# MicroD-25_Breakout_board.net
KiCad netlist of a schematic drawn in EAGLE
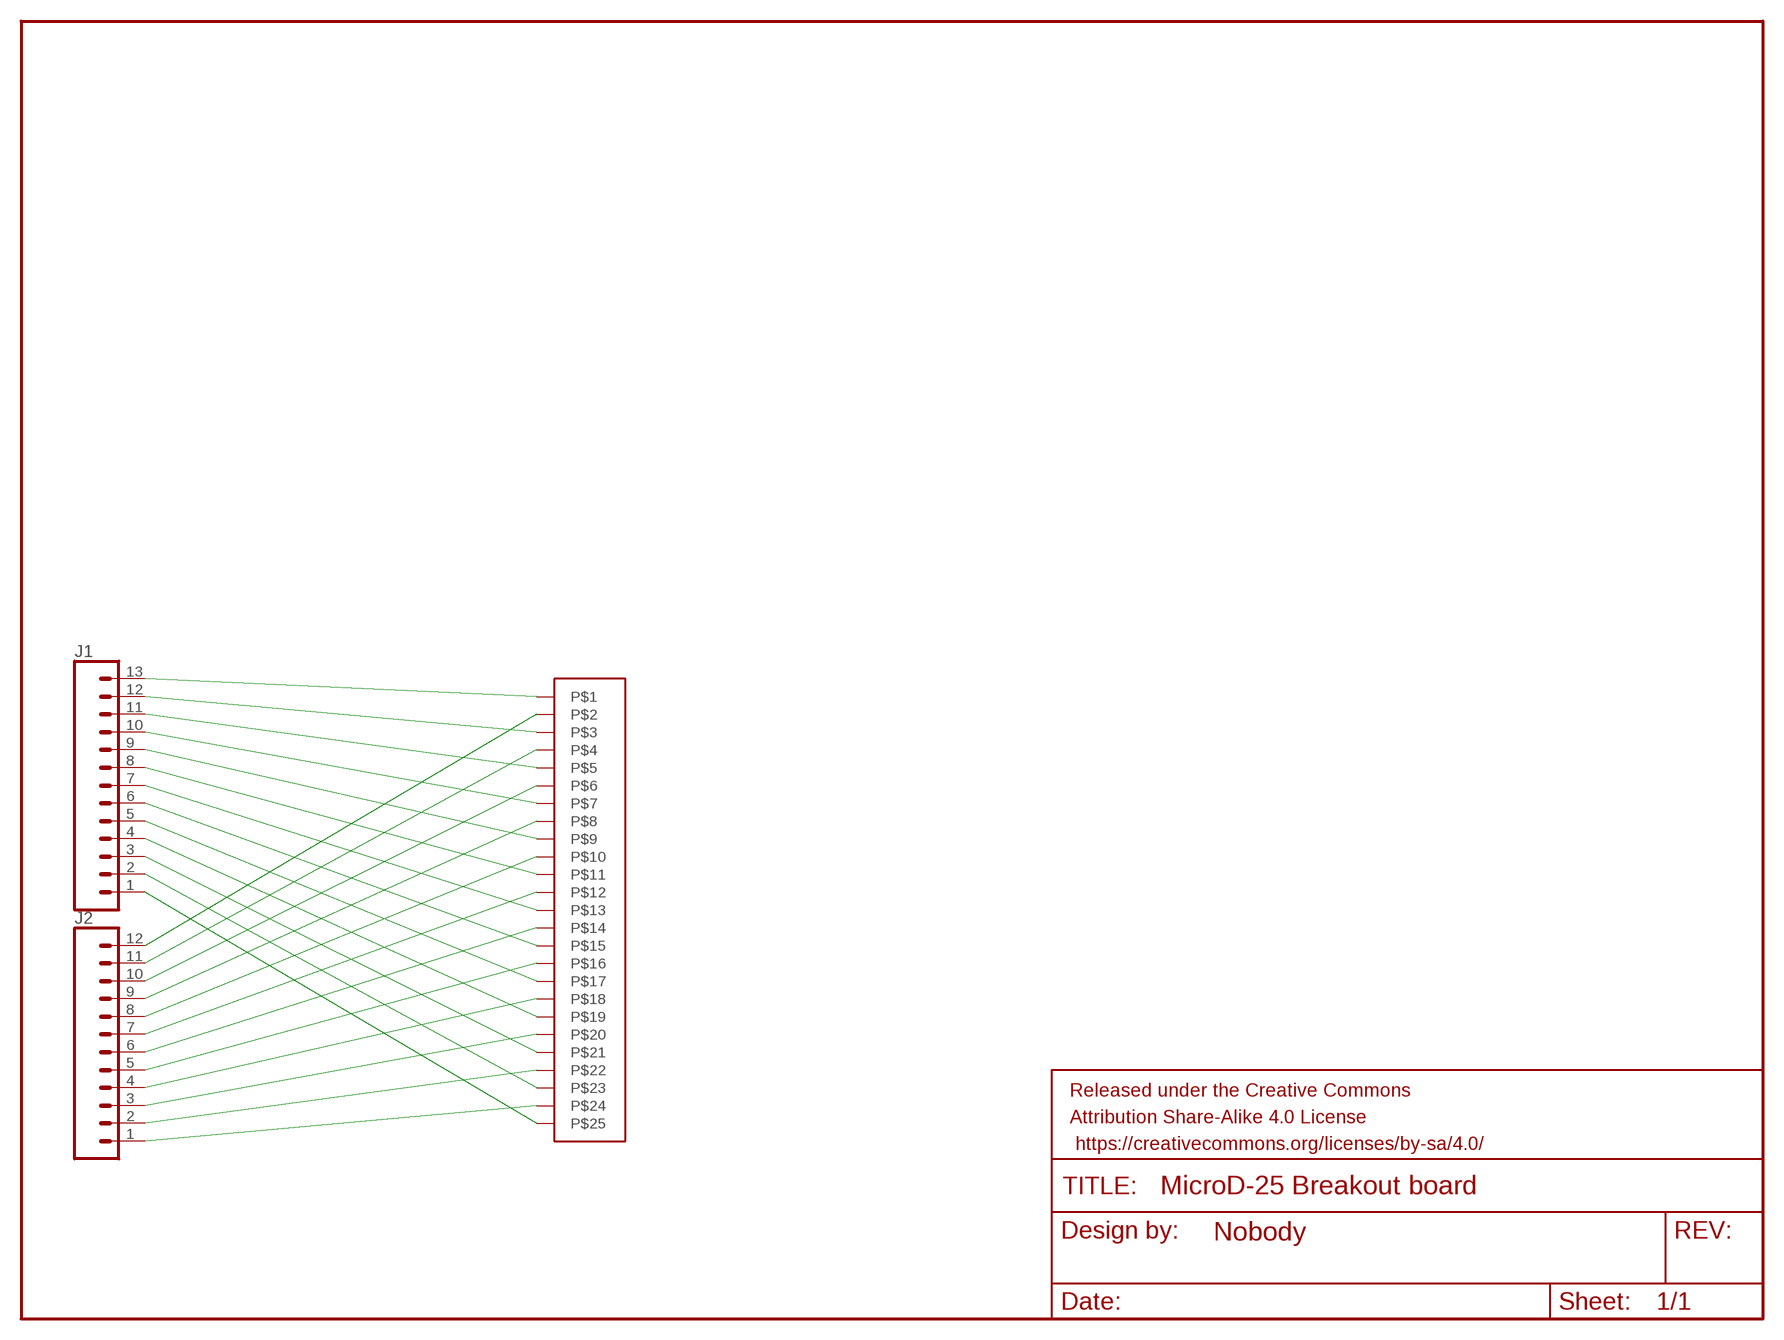
[diagram p0: schematic, sheet 1]

(export (version "E")
  (design (tool "Eeschema 10.0.6"))
  (components
    (comp (ref "FRAME1")
      (value "FRAME-LETTERNO_PACKAGE")
      (footprint "eagle-import:DUMMY")
      (fields (field (name "DESIGNER") "Nobody"))
      (libsource (lib "eagle-import") (part "FRAME-LETTERNO_PACKAGE"))
    )
    (comp (ref "J1")
      (value "CONN_13LONGPADS")
      (footprint "eagle-import:1X13-LONGPADS")
      (libsource (lib "eagle-import") (part "CONN_13LONGPADS"))
    )
    (comp (ref "J2")
      (value "CONN_12LONGPADS")
      (footprint "eagle-import:1X12_LONGPADS")
      (libsource (lib "eagle-import") (part "CONN_12LONGPADS"))
    )
    (comp (ref "U$1")
      (value "MICROD25_FM_RCPT")
      (footprint "eagle-import:MICROD25_FM_RCPT")
      (libsource (lib "eagle-import") (part "MICROD25_FM_RCPT"))
    )
  )
  (nets
    (net (code "1") (name "Net-(U$1-P$1)") (class "Default")
      (node (ref "J1") (pin "13") (pinfunction "13_13") (pintype "passive"))
      (node (ref "U$1") (pin "PIN1") (pinfunction "P$1_PIN1") (pintype "bidirectional"))
    )
    (net (code "2") (name "Net-(U$1-P$2)") (class "Default")
      (node (ref "J2") (pin "12") (pinfunction "12_12") (pintype "passive"))
      (node (ref "U$1") (pin "PIN2") (pinfunction "P$2_PIN2") (pintype "bidirectional"))
    )
    (net (code "3") (name "Net-(U$1-P$3)") (class "Default")
      (node (ref "J1") (pin "12") (pinfunction "12_12") (pintype "passive"))
      (node (ref "U$1") (pin "PIN3") (pinfunction "P$3_PIN3") (pintype "bidirectional"))
    )
    (net (code "4") (name "Net-(U$1-P$4)") (class "Default")
      (node (ref "J2") (pin "11") (pinfunction "11_11") (pintype "passive"))
      (node (ref "U$1") (pin "PIN4") (pinfunction "P$4_PIN4") (pintype "bidirectional"))
    )
    (net (code "5") (name "Net-(U$1-P$5)") (class "Default")
      (node (ref "J1") (pin "11") (pinfunction "11_11") (pintype "passive"))
      (node (ref "U$1") (pin "PIN5") (pinfunction "P$5_PIN5") (pintype "bidirectional"))
    )
    (net (code "6") (name "Net-(U$1-P$6)") (class "Default")
      (node (ref "J2") (pin "10") (pinfunction "10_10") (pintype "passive"))
      (node (ref "U$1") (pin "PIN6") (pinfunction "P$6_PIN6") (pintype "bidirectional"))
    )
    (net (code "7") (name "Net-(U$1-P$7)") (class "Default")
      (node (ref "J1") (pin "10") (pinfunction "10_10") (pintype "passive"))
      (node (ref "U$1") (pin "PIN7") (pinfunction "P$7_PIN7") (pintype "bidirectional"))
    )
    (net (code "8") (name "Net-(U$1-P$8)") (class "Default")
      (node (ref "J2") (pin "9") (pinfunction "9_9") (pintype "passive"))
      (node (ref "U$1") (pin "PIN8") (pinfunction "P$8_PIN8") (pintype "bidirectional"))
    )
    (net (code "9") (name "Net-(U$1-P$9)") (class "Default")
      (node (ref "J1") (pin "9") (pinfunction "9_9") (pintype "passive"))
      (node (ref "U$1") (pin "PIN9") (pinfunction "P$9_PIN9") (pintype "bidirectional"))
    )
    (net (code "10") (name "Net-(U$1-P$10)") (class "Default")
      (node (ref "J2") (pin "8") (pinfunction "8_8") (pintype "passive"))
      (node (ref "U$1") (pin "PIN10") (pinfunction "P$10_PIN10") (pintype "bidirectional"))
    )
    (net (code "11") (name "Net-(U$1-P$11)") (class "Default")
      (node (ref "J1") (pin "8") (pinfunction "8_8") (pintype "passive"))
      (node (ref "U$1") (pin "PIN11") (pinfunction "P$11_PIN11") (pintype "bidirectional"))
    )
    (net (code "12") (name "Net-(U$1-P$12)") (class "Default")
      (node (ref "J2") (pin "7") (pinfunction "7_7") (pintype "passive"))
      (node (ref "U$1") (pin "PIN12") (pinfunction "P$12_PIN12") (pintype "bidirectional"))
    )
    (net (code "13") (name "Net-(U$1-P$13)") (class "Default")
      (node (ref "J1") (pin "7") (pinfunction "7_7") (pintype "passive"))
      (node (ref "U$1") (pin "PIN13") (pinfunction "P$13_PIN13") (pintype "bidirectional"))
    )
    (net (code "14") (name "Net-(U$1-P$14)") (class "Default")
      (node (ref "J2") (pin "6") (pinfunction "6_6") (pintype "passive"))
      (node (ref "U$1") (pin "PIN14") (pinfunction "P$14_PIN14") (pintype "bidirectional"))
    )
    (net (code "15") (name "Net-(U$1-P$15)") (class "Default")
      (node (ref "J1") (pin "6") (pinfunction "6_6") (pintype "passive"))
      (node (ref "U$1") (pin "PIN15") (pinfunction "P$15_PIN15") (pintype "bidirectional"))
    )
    (net (code "16") (name "Net-(U$1-P$16)") (class "Default")
      (node (ref "J2") (pin "5") (pinfunction "5_5") (pintype "passive"))
      (node (ref "U$1") (pin "PIN16") (pinfunction "P$16_PIN16") (pintype "bidirectional"))
    )
    (net (code "17") (name "Net-(U$1-P$17)") (class "Default")
      (node (ref "J1") (pin "5") (pinfunction "5_5") (pintype "passive"))
      (node (ref "U$1") (pin "PIN17") (pinfunction "P$17_PIN17") (pintype "bidirectional"))
    )
    (net (code "18") (name "Net-(U$1-P$18)") (class "Default")
      (node (ref "J2") (pin "4") (pinfunction "4_4") (pintype "passive"))
      (node (ref "U$1") (pin "PIN18") (pinfunction "P$18_PIN18") (pintype "bidirectional"))
    )
    (net (code "19") (name "Net-(U$1-P$19)") (class "Default")
      (node (ref "J1") (pin "4") (pinfunction "4_4") (pintype "passive"))
      (node (ref "U$1") (pin "PIN19") (pinfunction "P$19_PIN19") (pintype "bidirectional"))
    )
    (net (code "20") (name "Net-(U$1-P$20)") (class "Default")
      (node (ref "J2") (pin "3") (pinfunction "3_3") (pintype "passive"))
      (node (ref "U$1") (pin "PIN20") (pinfunction "P$20_PIN20") (pintype "bidirectional"))
    )
    (net (code "21") (name "Net-(U$1-P$21)") (class "Default")
      (node (ref "J1") (pin "3") (pinfunction "3_3") (pintype "passive"))
      (node (ref "U$1") (pin "PIN21") (pinfunction "P$21_PIN21") (pintype "bidirectional"))
    )
    (net (code "22") (name "Net-(U$1-P$22)") (class "Default")
      (node (ref "J2") (pin "2") (pinfunction "2_2") (pintype "passive"))
      (node (ref "U$1") (pin "PIN22") (pinfunction "P$22_PIN22") (pintype "bidirectional"))
    )
    (net (code "23") (name "Net-(U$1-P$23)") (class "Default")
      (node (ref "J1") (pin "2") (pinfunction "2_2") (pintype "passive"))
      (node (ref "U$1") (pin "PIN23") (pinfunction "P$23_PIN23") (pintype "bidirectional"))
    )
    (net (code "24") (name "Net-(U$1-P$24)") (class "Default")
      (node (ref "J2") (pin "1") (pinfunction "1_1") (pintype "passive"))
      (node (ref "U$1") (pin "PIN24") (pinfunction "P$24_PIN24") (pintype "bidirectional"))
    )
    (net (code "25") (name "Net-(U$1-P$25)") (class "Default")
      (node (ref "J1") (pin "1") (pinfunction "1_1") (pintype "passive"))
      (node (ref "U$1") (pin "PIN25") (pinfunction "P$25_PIN25") (pintype "bidirectional"))
    )
  )
)
